# power-monitor.net
KiCad netlist of a schematic drawn in EAGLE
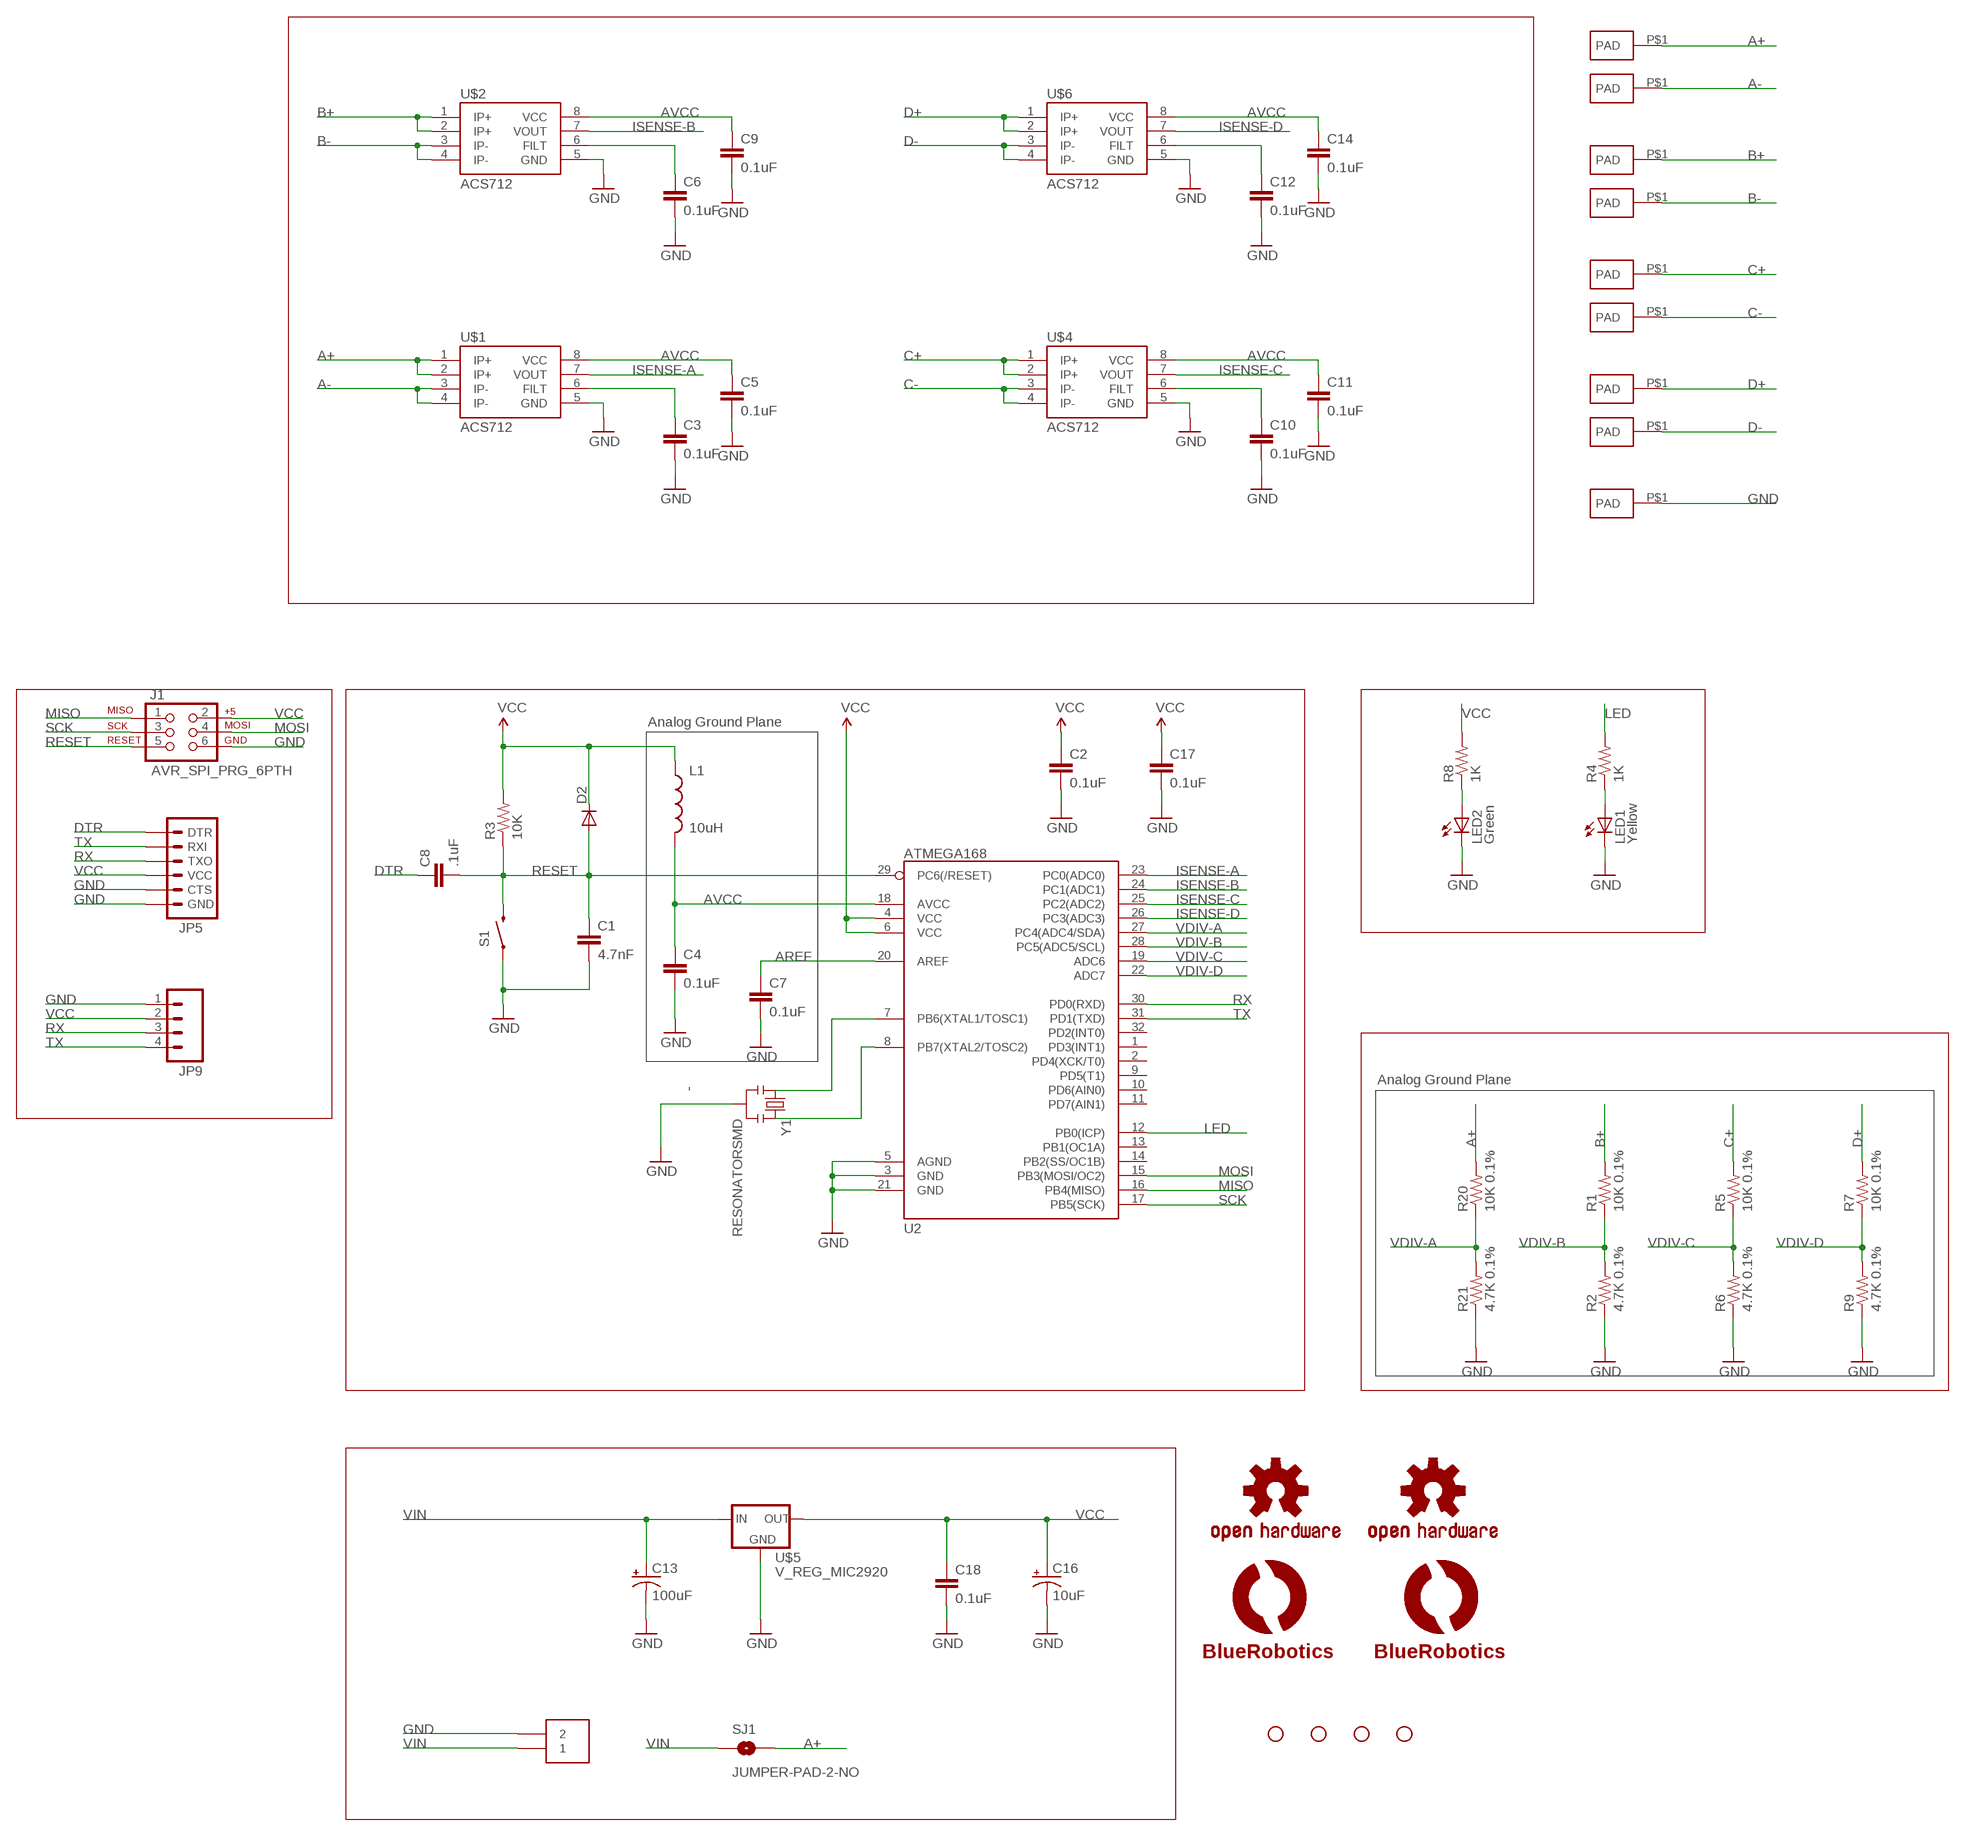
[diagram p0: schematic, sheet 1]

(export (version "E")
  (design (tool "Eeschema 10.0.6"))
  (components
    (comp (ref "C1")
      (value "4.7nF")
      (footprint "eagle-import:0603-CAP")
      (libsource (lib "eagle-import") (part "CAP0603-CAP"))
    )
    (comp (ref "C2")
      (value "0.1uF")
      (footprint "eagle-import:0603-CAP")
      (libsource (lib "eagle-import") (part "SparkFun2_CAP0603-CAP"))
    )
    (comp (ref "C3")
      (value "0.1uF")
      (footprint "eagle-import:0603-CAP")
      (libsource (lib "eagle-import") (part "SparkFun-Capacitors_CAP0603-CAP"))
    )
    (comp (ref "C4")
      (value "0.1uF")
      (footprint "eagle-import:0603-CAP")
      (libsource (lib "eagle-import") (part "CAP0603-CAP"))
    )
    (comp (ref "C5")
      (value "0.1uF")
      (footprint "eagle-import:0603-CAP")
      (libsource (lib "eagle-import") (part "SparkFun-Capacitors_CAP0603-CAP"))
    )
    (comp (ref "C6")
      (value "0.1uF")
      (footprint "eagle-import:0603-CAP")
      (libsource (lib "eagle-import") (part "SparkFun-Capacitors_CAP0603-CAP"))
    )
    (comp (ref "C7")
      (value "0.1uF")
      (footprint "eagle-import:0603-CAP")
      (libsource (lib "eagle-import") (part "CAP0603-CAP"))
    )
    (comp (ref "C8")
      (value ".1uF")
      (footprint "eagle-import:0603-CAP")
      (libsource (lib "eagle-import") (part "CAP0603-CAP"))
    )
    (comp (ref "C9")
      (value "0.1uF")
      (footprint "eagle-import:0603-CAP")
      (libsource (lib "eagle-import") (part "SparkFun-Capacitors_CAP0603-CAP"))
    )
    (comp (ref "C10")
      (value "0.1uF")
      (footprint "eagle-import:0603-CAP")
      (libsource (lib "eagle-import") (part "SparkFun-Capacitors_CAP0603-CAP"))
    )
    (comp (ref "C11")
      (value "0.1uF")
      (footprint "eagle-import:0603-CAP")
      (libsource (lib "eagle-import") (part "SparkFun-Capacitors_CAP0603-CAP"))
    )
    (comp (ref "C12")
      (value "0.1uF")
      (footprint "eagle-import:0603-CAP")
      (libsource (lib "eagle-import") (part "SparkFun-Capacitors_CAP0603-CAP"))
    )
    (comp (ref "C13")
      (value "100uF")
      (footprint "eagle-import:CPOL-RADIAL-100UF-25V")
      (libsource (lib "eagle-import") (part "CAP_POLPTH1"))
    )
    (comp (ref "C14")
      (value "0.1uF")
      (footprint "eagle-import:0603-CAP")
      (libsource (lib "eagle-import") (part "SparkFun-Capacitors_CAP0603-CAP"))
    )
    (comp (ref "C16")
      (value "10uF")
      (footprint "eagle-import:EIA3216")
      (libsource (lib "eagle-import") (part "CAP_POL1206"))
    )
    (comp (ref "C17")
      (value "0.1uF")
      (footprint "eagle-import:0603-CAP")
      (libsource (lib "eagle-import") (part "SparkFun2_CAP0603-CAP"))
    )
    (comp (ref "C18")
      (value "0.1uF")
      (footprint "eagle-import:0603-CAP")
      (libsource (lib "eagle-import") (part "CAP0603-CAP"))
    )
    (comp (ref "D2")
      (value "DIODESOD")
      (footprint "eagle-import:SOD-323")
      (libsource (lib "eagle-import") (part "DIODESOD"))
    )
    (comp (ref "J1")
      (value "AVR_SPI_PRG_6PTH")
      (footprint "eagle-import:2X3")
      (libsource (lib "eagle-import") (part "AVR_SPI_PRG_6PTH"))
    )
    (comp (ref "JP5")
      (value "ARDUINO_SERIAL_PROGRAMPTH")
      (footprint "eagle-import:1X06")
      (libsource (lib "eagle-import") (part "ARDUINO_SERIAL_PROGRAMPTH"))
    )
    (comp (ref "JP9")
      (value "M04PTH")
      (footprint "eagle-import:1X04")
      (libsource (lib "eagle-import") (part "M04PTH"))
    )
    (comp (ref "L1")
      (value "10uH")
      (footprint "eagle-import:0603")
      (libsource (lib "eagle-import") (part "INDUCTOR0603"))
    )
    (comp (ref "LED1")
      (value "Yellow")
      (footprint "eagle-import:LED-0603")
      (libsource (lib "eagle-import") (part "LED0603"))
    )
    (comp (ref "LED2")
      (value "Green")
      (footprint "eagle-import:LED-0603")
      (libsource (lib "eagle-import") (part "LED0603"))
    )
    (comp (ref "LOGO1")
      (value "OSHW-LOGOS")
      (footprint "eagle-import:OSHW-LOGO-S")
      (libsource (lib "eagle-import") (part "OSHW-LOGOS"))
    )
    (comp (ref "LOGO2")
      (value "OSHW-LOGOM")
      (footprint "eagle-import:OSHW-LOGO-M")
      (libsource (lib "eagle-import") (part "OSHW-LOGOM"))
    )
    (comp (ref "R1")
      (value "10K 0.1%")
      (footprint "eagle-import:0603-RES")
      (libsource (lib "eagle-import") (part "RESISTOR0603-RES"))
    )
    (comp (ref "R2")
      (value "4.7K 0.1%")
      (footprint "eagle-import:0603-RES")
      (libsource (lib "eagle-import") (part "RESISTOR0603-RES"))
    )
    (comp (ref "R3")
      (value "10K")
      (footprint "eagle-import:0603-RES")
      (libsource (lib "eagle-import") (part "RESISTOR0603-RES"))
    )
    (comp (ref "R4")
      (value "1K")
      (footprint "eagle-import:0603-RES")
      (libsource (lib "eagle-import") (part "RESISTOR0603-RES"))
    )
    (comp (ref "R5")
      (value "10K 0.1%")
      (footprint "eagle-import:0603-RES")
      (libsource (lib "eagle-import") (part "RESISTOR0603-RES"))
    )
    (comp (ref "R6")
      (value "4.7K 0.1%")
      (footprint "eagle-import:0603-RES")
      (libsource (lib "eagle-import") (part "RESISTOR0603-RES"))
    )
    (comp (ref "R7")
      (value "10K 0.1%")
      (footprint "eagle-import:0603-RES")
      (libsource (lib "eagle-import") (part "RESISTOR0603-RES"))
    )
    (comp (ref "R8")
      (value "1K")
      (footprint "eagle-import:0603-RES")
      (libsource (lib "eagle-import") (part "RESISTOR0603-RES"))
    )
    (comp (ref "R9")
      (value "4.7K 0.1%")
      (footprint "eagle-import:0603-RES")
      (libsource (lib "eagle-import") (part "RESISTOR0603-RES"))
    )
    (comp (ref "R20")
      (value "10K 0.1%")
      (footprint "eagle-import:0603-RES")
      (libsource (lib "eagle-import") (part "RESISTOR0603-RES"))
    )
    (comp (ref "R21")
      (value "4.7K 0.1%")
      (footprint "eagle-import:0603-RES")
      (libsource (lib "eagle-import") (part "RESISTOR0603-RES"))
    )
    (comp (ref "S1")
      (value "reset")
      (footprint "eagle-import:TACTILE_SWITCH_SMD")
      (libsource (lib "eagle-import") (part "SWITCH-MOMENTARY-2SMD"))
    )
    (comp (ref "SJ1")
      (value "JUMPER-PAD-2-NO")
      (footprint "eagle-import:PAD-JUMPER-2-NO_NO_SILK")
      (libsource (lib "eagle-import") (part "JUMPER-PAD-2-NO"))
    )
    (comp (ref "STANDOFF1")
      (value "STAND-OFF")
      (footprint "eagle-import:STAND-OFF")
      (libsource (lib "eagle-import") (part "STAND-OFF"))
    )
    (comp (ref "STANDOFF2")
      (value "STAND-OFF")
      (footprint "eagle-import:STAND-OFF")
      (libsource (lib "eagle-import") (part "STAND-OFF"))
    )
    (comp (ref "STANDOFF3")
      (value "STAND-OFF")
      (footprint "eagle-import:STAND-OFF")
      (libsource (lib "eagle-import") (part "STAND-OFF"))
    )
    (comp (ref "STANDOFF4")
      (value "STAND-OFF")
      (footprint "eagle-import:STAND-OFF")
      (libsource (lib "eagle-import") (part "STAND-OFF"))
    )
    (comp (ref "U$1")
      (value "ACS712")
      (footprint "eagle-import:SO08")
      (libsource (lib "eagle-import") (part "ACS712"))
    )
    (comp (ref "U$2")
      (value "ACS712")
      (footprint "eagle-import:SO08")
      (libsource (lib "eagle-import") (part "ACS712"))
    )
    (comp (ref "U$3")
      (value "TERMINAL-25MM-WEID")
      (footprint "eagle-import:LSF-SMT-5MM-2")
      (libsource (lib "eagle-import") (part "TERMINAL-25MM-WEID"))
    )
    (comp (ref "U$4")
      (value "ACS712")
      (footprint "eagle-import:SO08")
      (libsource (lib "eagle-import") (part "ACS712"))
    )
    (comp (ref "U$5")
      (value "V_REG_MIC2920")
      (footprint "eagle-import:SOT223")
      (libsource (lib "eagle-import") (part "V_REG_MIC2920"))
    )
    (comp (ref "U$6")
      (value "ACS712")
      (footprint "eagle-import:SO08")
      (libsource (lib "eagle-import") (part "ACS712"))
    )
    (comp (ref "U$7")
      (value "PADLARGE-ONE-SIDE")
      (footprint "eagle-import:PAD-0.2X0.3-ONE-SIDE")
      (libsource (lib "eagle-import") (part "PADLARGE-ONE-SIDE"))
    )
    (comp (ref "U$8")
      (value "PADLARGE-ONE-SIDE")
      (footprint "eagle-import:PAD-0.2X0.3-ONE-SIDE")
      (libsource (lib "eagle-import") (part "PADLARGE-ONE-SIDE"))
    )
    (comp (ref "U$9")
      (value "PADLARGE-ONE-SIDE")
      (footprint "eagle-import:PAD-0.2X0.3-ONE-SIDE")
      (libsource (lib "eagle-import") (part "PADLARGE-ONE-SIDE"))
    )
    (comp (ref "U$10")
      (value "PADLARGE-ONE-SIDE")
      (footprint "eagle-import:PAD-0.2X0.3-ONE-SIDE")
      (libsource (lib "eagle-import") (part "PADLARGE-ONE-SIDE"))
    )
    (comp (ref "U$11")
      (value "PADLARGE-ONE-SIDE")
      (footprint "eagle-import:PAD-0.2X0.3-ONE-SIDE")
      (libsource (lib "eagle-import") (part "PADLARGE-ONE-SIDE"))
    )
    (comp (ref "U$13")
      (value "PADLARGE-ONE-SIDE")
      (footprint "eagle-import:PAD-0.2X0.3-ONE-SIDE")
      (libsource (lib "eagle-import") (part "PADLARGE-ONE-SIDE"))
    )
    (comp (ref "U$14")
      (value "PADLARGE-ONE-SIDE")
      (footprint "eagle-import:PAD-0.2X0.3-ONE-SIDE")
      (libsource (lib "eagle-import") (part "PADLARGE-ONE-SIDE"))
    )
    (comp (ref "U$15")
      (value "PADLARGE-ONE-SIDE")
      (footprint "eagle-import:PAD-0.2X0.3-ONE-SIDE")
      (libsource (lib "eagle-import") (part "PADLARGE-ONE-SIDE"))
    )
    (comp (ref "U$16")
      (value "PADLARGE-ONE-SIDE")
      (footprint "eagle-import:PAD-0.2X0.3-ONE-SIDE")
      (libsource (lib "eagle-import") (part "PADLARGE-ONE-SIDE"))
    )
    (comp (ref "U$17")
      (value "LOGOBR-LOGO-M")
      (footprint "eagle-import:BR-LOGO-MEDIUM")
      (libsource (lib "eagle-import") (part "LOGOBR-LOGO-M"))
    )
    (comp (ref "U$18")
      (value "LOGOBR-LOGO-S")
      (footprint "eagle-import:BR-LOGO-SMALL")
      (libsource (lib "eagle-import") (part "LOGOBR-LOGO-S"))
    )
    (comp (ref "U2")
      (value "ATMEGA168")
      (footprint "eagle-import:TQFP32-08")
      (libsource (lib "eagle-import") (part "ATMEGA168"))
    )
    (comp (ref "Y1")
      (value "RESONATORSMD")
      (footprint "eagle-import:RESONATOR-SMD")
      (libsource (lib "eagle-import") (part "RESONATORSMD"))
    )
  )
  (nets
    (net (code "1") (name "/A+") (class "Default")
      (node (ref "R20") (pin "2") (pinfunction "2_2") (pintype "passive"))
      (node (ref "SJ1") (pin "2") (pinfunction "2_2") (pintype "passive"))
      (node (ref "U$1") (pin "1") (pinfunction "IP+_1") (pintype "bidirectional"))
      (node (ref "U$1") (pin "2") (pinfunction "IP+_2") (pintype "bidirectional"))
      (node (ref "U$13") (pin "P$1") (pinfunction "PAD_P$1") (pintype "bidirectional"))
    )
    (net (code "2") (name "/A-") (class "Default")
      (node (ref "U$1") (pin "3") (pinfunction "IP-_3") (pintype "bidirectional"))
      (node (ref "U$1") (pin "4") (pinfunction "IP-_4") (pintype "bidirectional"))
      (node (ref "U$14") (pin "P$1") (pinfunction "PAD_P$1") (pintype "bidirectional"))
    )
    (net (code "3") (name "/AREF") (class "Default")
      (node (ref "C7") (pin "1") (pinfunction "1_1") (pintype "passive"))
      (node (ref "U2") (pin "20") (pinfunction "AREF_20") (pintype "bidirectional"))
    )
    (net (code "4") (name "/AVCC") (class "Default")
      (node (ref "C11") (pin "1") (pinfunction "1_1") (pintype "passive"))
      (node (ref "C14") (pin "1") (pinfunction "1_1") (pintype "passive"))
      (node (ref "C4") (pin "1") (pinfunction "1_1") (pintype "passive"))
      (node (ref "C5") (pin "1") (pinfunction "1_1") (pintype "passive"))
      (node (ref "C9") (pin "1") (pinfunction "1_1") (pintype "passive"))
      (node (ref "L1") (pin "2") (pinfunction "2_2") (pintype "passive"))
      (node (ref "U$1") (pin "8") (pinfunction "VCC_8") (pintype "bidirectional"))
      (node (ref "U$2") (pin "8") (pinfunction "VCC_8") (pintype "bidirectional"))
      (node (ref "U$4") (pin "8") (pinfunction "VCC_8") (pintype "bidirectional"))
      (node (ref "U$6") (pin "8") (pinfunction "VCC_8") (pintype "bidirectional"))
      (node (ref "U2") (pin "18") (pinfunction "AVCC_18") (pintype "bidirectional"))
    )
    (net (code "5") (name "/B+") (class "Default")
      (node (ref "R1") (pin "2") (pinfunction "2_2") (pintype "passive"))
      (node (ref "U$15") (pin "P$1") (pinfunction "PAD_P$1") (pintype "bidirectional"))
      (node (ref "U$2") (pin "1") (pinfunction "IP+_1") (pintype "bidirectional"))
      (node (ref "U$2") (pin "2") (pinfunction "IP+_2") (pintype "bidirectional"))
    )
    (net (code "6") (name "/B-") (class "Default")
      (node (ref "U$16") (pin "P$1") (pinfunction "PAD_P$1") (pintype "bidirectional"))
      (node (ref "U$2") (pin "3") (pinfunction "IP-_3") (pintype "bidirectional"))
      (node (ref "U$2") (pin "4") (pinfunction "IP-_4") (pintype "bidirectional"))
    )
    (net (code "7") (name "/C+") (class "Default")
      (node (ref "R5") (pin "2") (pinfunction "2_2") (pintype "passive"))
      (node (ref "U$4") (pin "1") (pinfunction "IP+_1") (pintype "bidirectional"))
      (node (ref "U$4") (pin "2") (pinfunction "IP+_2") (pintype "bidirectional"))
      (node (ref "U$7") (pin "P$1") (pinfunction "PAD_P$1") (pintype "bidirectional"))
    )
    (net (code "8") (name "/C-") (class "Default")
      (node (ref "U$4") (pin "3") (pinfunction "IP-_3") (pintype "bidirectional"))
      (node (ref "U$4") (pin "4") (pinfunction "IP-_4") (pintype "bidirectional"))
      (node (ref "U$8") (pin "P$1") (pinfunction "PAD_P$1") (pintype "bidirectional"))
    )
    (net (code "9") (name "/D+") (class "Default")
      (node (ref "R7") (pin "2") (pinfunction "2_2") (pintype "passive"))
      (node (ref "U$6") (pin "1") (pinfunction "IP+_1") (pintype "bidirectional"))
      (node (ref "U$6") (pin "2") (pinfunction "IP+_2") (pintype "bidirectional"))
      (node (ref "U$9") (pin "P$1") (pinfunction "PAD_P$1") (pintype "bidirectional"))
    )
    (net (code "10") (name "/D-") (class "Default")
      (node (ref "U$10") (pin "P$1") (pinfunction "PAD_P$1") (pintype "bidirectional"))
      (node (ref "U$6") (pin "3") (pinfunction "IP-_3") (pintype "bidirectional"))
      (node (ref "U$6") (pin "4") (pinfunction "IP-_4") (pintype "bidirectional"))
    )
    (net (code "11") (name "/DTR") (class "Default")
      (node (ref "C8") (pin "1") (pinfunction "1_1") (pintype "passive"))
      (node (ref "JP5") (pin "1") (pinfunction "DTR_1") (pintype "passive"))
    )
    (net (code "12") (name "/ISENSE-A") (class "Default")
      (node (ref "U$1") (pin "7") (pinfunction "VOUT_7") (pintype "bidirectional"))
      (node (ref "U2") (pin "23") (pinfunction "PC0(ADC0)_23") (pintype "bidirectional"))
    )
    (net (code "13") (name "/ISENSE-B") (class "Default")
      (node (ref "U$2") (pin "7") (pinfunction "VOUT_7") (pintype "bidirectional"))
      (node (ref "U2") (pin "24") (pinfunction "PC1(ADC1)_24") (pintype "bidirectional"))
    )
    (net (code "14") (name "/ISENSE-C") (class "Default")
      (node (ref "U$4") (pin "7") (pinfunction "VOUT_7") (pintype "bidirectional"))
      (node (ref "U2") (pin "25") (pinfunction "PC2(ADC2)_25") (pintype "bidirectional"))
    )
    (net (code "15") (name "/ISENSE-D") (class "Default")
      (node (ref "U$6") (pin "7") (pinfunction "VOUT_7") (pintype "bidirectional"))
      (node (ref "U2") (pin "26") (pinfunction "PC3(ADC3)_26") (pintype "bidirectional"))
    )
    (net (code "16") (name "/LED") (class "Default")
      (node (ref "R4") (pin "2") (pinfunction "2_2") (pintype "passive"))
      (node (ref "U2") (pin "12") (pinfunction "PB0(ICP)_12") (pintype "bidirectional"))
    )
    (net (code "17") (name "/MISO") (class "Default")
      (node (ref "J1") (pin "1") (pinfunction "1_1") (pintype "passive"))
      (node (ref "U2") (pin "16") (pinfunction "PB4(MISO)_16") (pintype "bidirectional"))
    )
    (net (code "18") (name "/MOSI") (class "Default")
      (node (ref "J1") (pin "4") (pinfunction "4_4") (pintype "passive"))
      (node (ref "U2") (pin "15") (pinfunction "PB3(MOSI/OC2)_15") (pintype "bidirectional"))
    )
    (net (code "19") (name "/RESET") (class "Default")
      (node (ref "C1") (pin "1") (pinfunction "1_1") (pintype "passive"))
      (node (ref "C8") (pin "2") (pinfunction "2_2") (pintype "passive"))
      (node (ref "D2") (pin "2") (pinfunction "A_2") (pintype "passive"))
      (node (ref "J1") (pin "5") (pinfunction "5_5") (pintype "passive"))
      (node (ref "R3") (pin "1") (pinfunction "1_1") (pintype "passive"))
      (node (ref "S1") (pin "3") (pinfunction "2_3") (pintype "passive"))
      (node (ref "U2") (pin "29") (pinfunction "PC6(/RESET)_29") (pintype "bidirectional"))
    )
    (net (code "20") (name "/RX") (class "Default")
      (node (ref "JP5") (pin "3") (pinfunction "TXO_3") (pintype "passive"))
      (node (ref "JP9") (pin "3") (pinfunction "3_3") (pintype "passive"))
      (node (ref "U2") (pin "30") (pinfunction "PD0(RXD)_30") (pintype "bidirectional"))
    )
    (net (code "21") (name "/SCK") (class "Default")
      (node (ref "J1") (pin "3") (pinfunction "3_3") (pintype "passive"))
      (node (ref "U2") (pin "17") (pinfunction "PB5(SCK)_17") (pintype "bidirectional"))
    )
    (net (code "22") (name "/TX") (class "Default")
      (node (ref "JP5") (pin "2") (pinfunction "RXI_2") (pintype "passive"))
      (node (ref "JP9") (pin "4") (pinfunction "4_4") (pintype "passive"))
      (node (ref "U2") (pin "31") (pinfunction "PD1(TXD)_31") (pintype "bidirectional"))
    )
    (net (code "23") (name "/VDIV-A") (class "Default")
      (node (ref "R20") (pin "1") (pinfunction "1_1") (pintype "passive"))
      (node (ref "R21") (pin "2") (pinfunction "2_2") (pintype "passive"))
      (node (ref "U2") (pin "27") (pinfunction "PC4(ADC4/SDA)_27") (pintype "bidirectional"))
    )
    (net (code "24") (name "/VDIV-B") (class "Default")
      (node (ref "R1") (pin "1") (pinfunction "1_1") (pintype "passive"))
      (node (ref "R2") (pin "2") (pinfunction "2_2") (pintype "passive"))
      (node (ref "U2") (pin "28") (pinfunction "PC5(ADC5/SCL)_28") (pintype "bidirectional"))
    )
    (net (code "25") (name "/VDIV-C") (class "Default")
      (node (ref "R5") (pin "1") (pinfunction "1_1") (pintype "passive"))
      (node (ref "R6") (pin "2") (pinfunction "2_2") (pintype "passive"))
      (node (ref "U2") (pin "19") (pinfunction "ADC6_19") (pintype "bidirectional"))
    )
    (net (code "26") (name "/VDIV-D") (class "Default")
      (node (ref "R7") (pin "1") (pinfunction "1_1") (pintype "passive"))
      (node (ref "R9") (pin "2") (pinfunction "2_2") (pintype "passive"))
      (node (ref "U2") (pin "22") (pinfunction "ADC7_22") (pintype "bidirectional"))
    )
    (net (code "27") (name "/VIN") (class "Default")
      (node (ref "C13") (pin "1") (pinfunction "+_1") (pintype "passive"))
      (node (ref "SJ1") (pin "1") (pinfunction "1_1") (pintype "passive"))
      (node (ref "U$3") (pin "1") (pinfunction "1_1") (pintype "bidirectional"))
      (node (ref "U$3") (pin "3") (pinfunction "1_3") (pintype "bidirectional"))
      (node (ref "U$5") (pin "1") (pinfunction "IN_1") (pintype "input"))
    )
    (net (code "28") (name "GND") (class "Default")
      (node (ref "C1") (pin "2") (pinfunction "2_2") (pintype "passive"))
      (node (ref "C10") (pin "2") (pinfunction "2_2") (pintype "passive"))
      (node (ref "C11") (pin "2") (pinfunction "2_2") (pintype "passive"))
      (node (ref "C12") (pin "2") (pinfunction "2_2") (pintype "passive"))
      (node (ref "C13") (pin "2") (pinfunction "-_2") (pintype "passive"))
      (node (ref "C14") (pin "2") (pinfunction "2_2") (pintype "passive"))
      (node (ref "C16") (pin "C") (pinfunction "-_C") (pintype "passive"))
      (node (ref "C17") (pin "2") (pinfunction "2_2") (pintype "passive"))
      (node (ref "C18") (pin "2") (pinfunction "2_2") (pintype "passive"))
      (node (ref "C2") (pin "2") (pinfunction "2_2") (pintype "passive"))
      (node (ref "C3") (pin "2") (pinfunction "2_2") (pintype "passive"))
      (node (ref "C4") (pin "2") (pinfunction "2_2") (pintype "passive"))
      (node (ref "C5") (pin "2") (pinfunction "2_2") (pintype "passive"))
      (node (ref "C6") (pin "2") (pinfunction "2_2") (pintype "passive"))
      (node (ref "C7") (pin "2") (pinfunction "2_2") (pintype "passive"))
      (node (ref "C9") (pin "2") (pinfunction "2_2") (pintype "passive"))
      (node (ref "J1") (pin "6") (pinfunction "6_6") (pintype "passive"))
      (node (ref "JP5") (pin "5") (pinfunction "CTS_5") (pintype "passive"))
      (node (ref "JP5") (pin "6") (pinfunction "GND_6") (pintype "passive"))
      (node (ref "JP9") (pin "1") (pinfunction "1_1") (pintype "passive"))
      (node (ref "LED1") (pin "C") (pinfunction "C_C") (pintype "passive"))
      (node (ref "LED2") (pin "C") (pinfunction "C_C") (pintype "passive"))
      (node (ref "R2") (pin "1") (pinfunction "1_1") (pintype "passive"))
      (node (ref "R21") (pin "1") (pinfunction "1_1") (pintype "passive"))
      (node (ref "R6") (pin "1") (pinfunction "1_1") (pintype "passive"))
      (node (ref "R9") (pin "1") (pinfunction "1_1") (pintype "passive"))
      (node (ref "S1") (pin "1") (pinfunction "1_1") (pintype "passive"))
      (node (ref "U$1") (pin "5") (pinfunction "GND_5") (pintype "bidirectional"))
      (node (ref "U$11") (pin "P$1") (pinfunction "PAD_P$1") (pintype "bidirectional"))
      (node (ref "U$2") (pin "5") (pinfunction "GND_5") (pintype "bidirectional"))
      (node (ref "U$3") (pin "2") (pinfunction "2_2") (pintype "bidirectional"))
      (node (ref "U$3") (pin "4") (pinfunction "2_4") (pintype "bidirectional"))
      (node (ref "U$4") (pin "5") (pinfunction "GND_5") (pintype "bidirectional"))
      (node (ref "U$5") (pin "2") (pinfunction "GND_2") (pintype "input"))
      (node (ref "U$6") (pin "5") (pinfunction "GND_5") (pintype "bidirectional"))
      (node (ref "U2") (pin "21") (pinfunction "GND_21") (pintype "bidirectional"))
      (node (ref "U2") (pin "3") (pinfunction "GND_3") (pintype "bidirectional"))
      (node (ref "U2") (pin "5") (pinfunction "AGND_5") (pintype "bidirectional"))
      (node (ref "Y1") (pin "2") (pinfunction "2_2") (pintype "passive"))
    )
    (net (code "29") (name "Net-(LED1-PadA)") (class "Default")
      (node (ref "LED1") (pin "A") (pinfunction "A_A") (pintype "passive"))
      (node (ref "R4") (pin "1") (pinfunction "1_1") (pintype "passive"))
    )
    (net (code "30") (name "Net-(LED2-PadA)") (class "Default")
      (node (ref "LED2") (pin "A") (pinfunction "A_A") (pintype "passive"))
      (node (ref "R8") (pin "1") (pinfunction "1_1") (pintype "passive"))
    )
    (net (code "31") (name "Net-(U$1-FILT)") (class "Default")
      (node (ref "C3") (pin "1") (pinfunction "1_1") (pintype "passive"))
      (node (ref "U$1") (pin "6") (pinfunction "FILT_6") (pintype "bidirectional"))
    )
    (net (code "32") (name "Net-(U$2-FILT)") (class "Default")
      (node (ref "C6") (pin "1") (pinfunction "1_1") (pintype "passive"))
      (node (ref "U$2") (pin "6") (pinfunction "FILT_6") (pintype "bidirectional"))
    )
    (net (code "33") (name "Net-(U$4-FILT)") (class "Default")
      (node (ref "C10") (pin "1") (pinfunction "1_1") (pintype "passive"))
      (node (ref "U$4") (pin "6") (pinfunction "FILT_6") (pintype "bidirectional"))
    )
    (net (code "34") (name "Net-(U$6-FILT)") (class "Default")
      (node (ref "C12") (pin "1") (pinfunction "1_1") (pintype "passive"))
      (node (ref "U$6") (pin "6") (pinfunction "FILT_6") (pintype "bidirectional"))
    )
    (net (code "35") (name "Net-(U2-PB6(XTAL1{slash}TOSC1))") (class "Default")
      (node (ref "U2") (pin "7") (pinfunction "PB6(XTAL1/TOSC1)_7") (pintype "bidirectional"))
      (node (ref "Y1") (pin "1") (pinfunction "1_1") (pintype "passive"))
    )
    (net (code "36") (name "Net-(U2-PB7(XTAL2{slash}TOSC2))") (class "Default")
      (node (ref "U2") (pin "8") (pinfunction "PB7(XTAL2/TOSC2)_8") (pintype "bidirectional"))
      (node (ref "Y1") (pin "3") (pinfunction "3_3") (pintype "passive"))
    )
    (net (code "37") (name "VCC") (class "Default")
      (node (ref "C16") (pin "A") (pinfunction "+_A") (pintype "passive"))
      (node (ref "C17") (pin "1") (pinfunction "1_1") (pintype "passive"))
      (node (ref "C18") (pin "1") (pinfunction "1_1") (pintype "passive"))
      (node (ref "C2") (pin "1") (pinfunction "1_1") (pintype "passive"))
      (node (ref "D2") (pin "1") (pinfunction "C_1") (pintype "passive"))
      (node (ref "J1") (pin "2") (pinfunction "2_2") (pintype "passive"))
      (node (ref "JP5") (pin "4") (pinfunction "VCC_4") (pintype "passive"))
      (node (ref "JP9") (pin "2") (pinfunction "2_2") (pintype "passive"))
      (node (ref "L1") (pin "1") (pinfunction "1_1") (pintype "passive"))
      (node (ref "R3") (pin "2") (pinfunction "2_2") (pintype "passive"))
      (node (ref "R8") (pin "2") (pinfunction "2_2") (pintype "passive"))
      (node (ref "U$5") (pin "3") (pinfunction "OUT_3") (pintype "output"))
      (node (ref "U2") (pin "4") (pinfunction "VCC_4") (pintype "bidirectional"))
      (node (ref "U2") (pin "6") (pinfunction "VCC_6") (pintype "bidirectional"))
    )
    (net (code "38") (name "unconnected-(U2-PB1(OC1A)-Pad13)") (class "Default")
      (node (ref "U2") (pin "13") (pinfunction "PB1(OC1A)_13") (pintype "bidirectional"))
    )
    (net (code "39") (name "unconnected-(U2-PB2(SS{slash}OC1B)-Pad14)") (class "Default")
      (node (ref "U2") (pin "14") (pinfunction "PB2(SS/OC1B)_14") (pintype "bidirectional"))
    )
    (net (code "40") (name "unconnected-(U2-PD2(INT0)-Pad32)") (class "Default")
      (node (ref "U2") (pin "32") (pinfunction "PD2(INT0)_32") (pintype "bidirectional"))
    )
    (net (code "41") (name "unconnected-(U2-PD3(INT1)-Pad1)") (class "Default")
      (node (ref "U2") (pin "1") (pinfunction "PD3(INT1)_1") (pintype "bidirectional"))
    )
    (net (code "42") (name "unconnected-(U2-PD4(XCK{slash}T0)-Pad2)") (class "Default")
      (node (ref "U2") (pin "2") (pinfunction "PD4(XCK/T0)_2") (pintype "bidirectional"))
    )
    (net (code "43") (name "unconnected-(U2-PD5(T1)-Pad9)") (class "Default")
      (node (ref "U2") (pin "9") (pinfunction "PD5(T1)_9") (pintype "bidirectional"))
    )
    (net (code "44") (name "unconnected-(U2-PD6(AIN0)-Pad10)") (class "Default")
      (node (ref "U2") (pin "10") (pinfunction "PD6(AIN0)_10") (pintype "bidirectional"))
    )
    (net (code "45") (name "unconnected-(U2-PD7(AIN1)-Pad11)") (class "Default")
      (node (ref "U2") (pin "11") (pinfunction "PD7(AIN1)_11") (pintype "bidirectional"))
    )
  )
)
